# Schematic.net
KiCad netlist of a schematic drawn in EAGLE
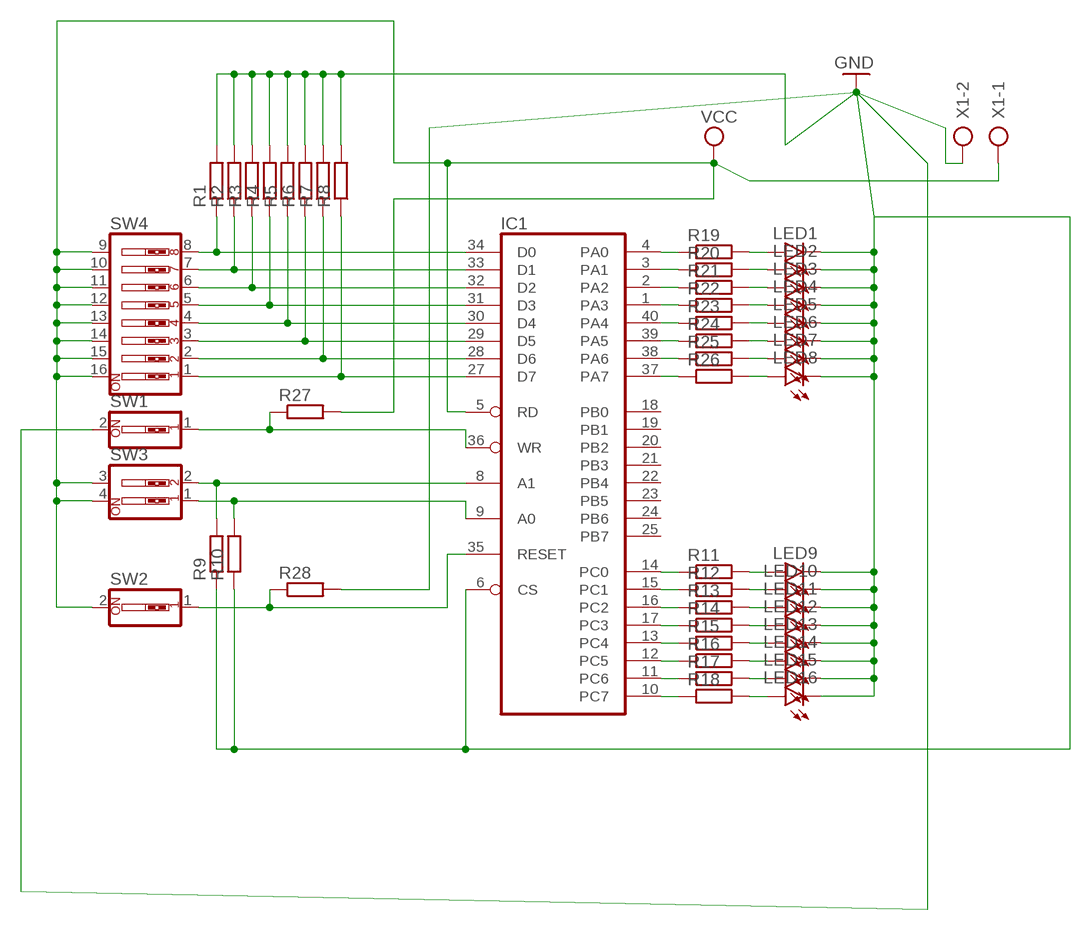
[diagram p0: schematic, sheet 1]

(export (version "E")
  (design (tool "Eeschema 10.0.6"))
  (components
    (comp (ref "IC1")
      (value "8255A")
      (footprint "eagle-import:DIL40")
      (libsource (lib "eagle-import") (part "8255A"))
    )
    (comp (ref "LED1")
      (value "LED5MM")
      (footprint "eagle-import:LED5MM")
      (libsource (lib "eagle-import") (part "LED5MM"))
    )
    (comp (ref "LED2")
      (value "LED5MM")
      (footprint "eagle-import:LED5MM")
      (libsource (lib "eagle-import") (part "LED5MM"))
    )
    (comp (ref "LED3")
      (value "LED5MM")
      (footprint "eagle-import:LED5MM")
      (libsource (lib "eagle-import") (part "LED5MM"))
    )
    (comp (ref "LED4")
      (value "LED5MM")
      (footprint "eagle-import:LED5MM")
      (libsource (lib "eagle-import") (part "LED5MM"))
    )
    (comp (ref "LED5")
      (value "LED5MM")
      (footprint "eagle-import:LED5MM")
      (libsource (lib "eagle-import") (part "LED5MM"))
    )
    (comp (ref "LED6")
      (value "LED5MM")
      (footprint "eagle-import:LED5MM")
      (libsource (lib "eagle-import") (part "LED5MM"))
    )
    (comp (ref "LED7")
      (value "LED5MM")
      (footprint "eagle-import:LED5MM")
      (libsource (lib "eagle-import") (part "LED5MM"))
    )
    (comp (ref "LED8")
      (value "LED5MM")
      (footprint "eagle-import:LED5MM")
      (libsource (lib "eagle-import") (part "LED5MM"))
    )
    (comp (ref "LED9")
      (value "LED5MM")
      (footprint "eagle-import:LED5MM")
      (libsource (lib "eagle-import") (part "LED5MM"))
    )
    (comp (ref "LED10")
      (value "LED5MM")
      (footprint "eagle-import:LED5MM")
      (libsource (lib "eagle-import") (part "LED5MM"))
    )
    (comp (ref "LED11")
      (value "LED5MM")
      (footprint "eagle-import:LED5MM")
      (libsource (lib "eagle-import") (part "LED5MM"))
    )
    (comp (ref "LED12")
      (value "LED5MM")
      (footprint "eagle-import:LED5MM")
      (libsource (lib "eagle-import") (part "LED5MM"))
    )
    (comp (ref "LED13")
      (value "LED5MM")
      (footprint "eagle-import:LED5MM")
      (libsource (lib "eagle-import") (part "LED5MM"))
    )
    (comp (ref "LED14")
      (value "LED5MM")
      (footprint "eagle-import:LED5MM")
      (libsource (lib "eagle-import") (part "LED5MM"))
    )
    (comp (ref "LED15")
      (value "LED5MM")
      (footprint "eagle-import:LED5MM")
      (libsource (lib "eagle-import") (part "LED5MM"))
    )
    (comp (ref "LED16")
      (value "LED5MM")
      (footprint "eagle-import:LED5MM")
      (libsource (lib "eagle-import") (part "LED5MM"))
    )
    (comp (ref "R1")
      (value "R-EU_0207/10")
      (footprint "eagle-import:0207_10")
      (libsource (lib "eagle-import") (part "R-EU_0207/10"))
    )
    (comp (ref "R2")
      (value "R-EU_0207/10")
      (footprint "eagle-import:0207_10")
      (libsource (lib "eagle-import") (part "R-EU_0207/10"))
    )
    (comp (ref "R3")
      (value "R-EU_0207/10")
      (footprint "eagle-import:0207_10")
      (libsource (lib "eagle-import") (part "R-EU_0207/10"))
    )
    (comp (ref "R4")
      (value "R-EU_0207/10")
      (footprint "eagle-import:0207_10")
      (libsource (lib "eagle-import") (part "R-EU_0207/10"))
    )
    (comp (ref "R5")
      (value "R-EU_0207/10")
      (footprint "eagle-import:0207_10")
      (libsource (lib "eagle-import") (part "R-EU_0207/10"))
    )
    (comp (ref "R6")
      (value "R-EU_0207/10")
      (footprint "eagle-import:0207_10")
      (libsource (lib "eagle-import") (part "R-EU_0207/10"))
    )
    (comp (ref "R7")
      (value "R-EU_0207/10")
      (footprint "eagle-import:0207_10")
      (libsource (lib "eagle-import") (part "R-EU_0207/10"))
    )
    (comp (ref "R8")
      (value "R-EU_0207/10")
      (footprint "eagle-import:0207_10")
      (libsource (lib "eagle-import") (part "R-EU_0207/10"))
    )
    (comp (ref "R9")
      (value "R-EU_0207/10")
      (footprint "eagle-import:0207_10")
      (libsource (lib "eagle-import") (part "R-EU_0207/10"))
    )
    (comp (ref "R10")
      (value "R-EU_0207/10")
      (footprint "eagle-import:0207_10")
      (libsource (lib "eagle-import") (part "R-EU_0207/10"))
    )
    (comp (ref "R11")
      (value "R-EU_0207/10")
      (footprint "eagle-import:0207_10")
      (libsource (lib "eagle-import") (part "R-EU_0207/10"))
    )
    (comp (ref "R12")
      (value "R-EU_0207/10")
      (footprint "eagle-import:0207_10")
      (libsource (lib "eagle-import") (part "R-EU_0207/10"))
    )
    (comp (ref "R13")
      (value "R-EU_0207/10")
      (footprint "eagle-import:0207_10")
      (libsource (lib "eagle-import") (part "R-EU_0207/10"))
    )
    (comp (ref "R14")
      (value "R-EU_0207/10")
      (footprint "eagle-import:0207_10")
      (libsource (lib "eagle-import") (part "R-EU_0207/10"))
    )
    (comp (ref "R15")
      (value "R-EU_0207/10")
      (footprint "eagle-import:0207_10")
      (libsource (lib "eagle-import") (part "R-EU_0207/10"))
    )
    (comp (ref "R16")
      (value "R-EU_0207/10")
      (footprint "eagle-import:0207_10")
      (libsource (lib "eagle-import") (part "R-EU_0207/10"))
    )
    (comp (ref "R17")
      (value "R-EU_0207/10")
      (footprint "eagle-import:0207_10")
      (libsource (lib "eagle-import") (part "R-EU_0207/10"))
    )
    (comp (ref "R18")
      (value "R-EU_0207/10")
      (footprint "eagle-import:0207_10")
      (libsource (lib "eagle-import") (part "R-EU_0207/10"))
    )
    (comp (ref "R19")
      (value "R-EU_0207/10")
      (footprint "eagle-import:0207_10")
      (libsource (lib "eagle-import") (part "R-EU_0207/10"))
    )
    (comp (ref "R20")
      (value "R-EU_0207/10")
      (footprint "eagle-import:0207_10")
      (libsource (lib "eagle-import") (part "R-EU_0207/10"))
    )
    (comp (ref "R21")
      (value "R-EU_0207/10")
      (footprint "eagle-import:0207_10")
      (libsource (lib "eagle-import") (part "R-EU_0207/10"))
    )
    (comp (ref "R22")
      (value "R-EU_0207/10")
      (footprint "eagle-import:0207_10")
      (libsource (lib "eagle-import") (part "R-EU_0207/10"))
    )
    (comp (ref "R23")
      (value "R-EU_0207/10")
      (footprint "eagle-import:0207_10")
      (libsource (lib "eagle-import") (part "R-EU_0207/10"))
    )
    (comp (ref "R24")
      (value "R-EU_0207/10")
      (footprint "eagle-import:0207_10")
      (libsource (lib "eagle-import") (part "R-EU_0207/10"))
    )
    (comp (ref "R25")
      (value "R-EU_0207/10")
      (footprint "eagle-import:0207_10")
      (libsource (lib "eagle-import") (part "R-EU_0207/10"))
    )
    (comp (ref "R26")
      (value "R-EU_0207/10")
      (footprint "eagle-import:0207_10")
      (libsource (lib "eagle-import") (part "R-EU_0207/10"))
    )
    (comp (ref "R27")
      (value "R-EU_0207/10")
      (footprint "eagle-import:0207_10")
      (libsource (lib "eagle-import") (part "R-EU_0207/10"))
    )
    (comp (ref "R28")
      (value "R-EU_0207/10")
      (footprint "eagle-import:0207_10")
      (libsource (lib "eagle-import") (part "R-EU_0207/10"))
    )
    (comp (ref "SW1")
      (value "SW_DIP-1")
      (footprint "eagle-import:EDG-01")
      (libsource (lib "eagle-import") (part "SW_DIP-1"))
    )
    (comp (ref "SW2")
      (value "SW_DIP-1")
      (footprint "eagle-import:EDG-01")
      (libsource (lib "eagle-import") (part "SW_DIP-1"))
    )
    (comp (ref "SW3")
      (value "SW_DIP-2")
      (footprint "eagle-import:EDG-02")
      (libsource (lib "eagle-import") (part "SW_DIP-2"))
    )
    (comp (ref "SW4")
      (value "SW_DIP-8")
      (footprint "eagle-import:EDG-08")
      (libsource (lib "eagle-import") (part "SW_DIP-8"))
    )
    (comp (ref "X1")
      (value "AK500/2")
      (footprint "eagle-import:AK500_2")
      (libsource (lib "eagle-import") (part "AK500/2"))
    )
  )
  (nets
    (net (code "1") (name "GND") (class "Default")
      (node (ref "IC1") (pin "6") (pinfunction "CS_6") (pintype "input"))
      (node (ref "LED1") (pin "K") (pinfunction "C_K") (pintype "passive"))
      (node (ref "LED10") (pin "K") (pinfunction "C_K") (pintype "passive"))
      (node (ref "LED11") (pin "K") (pinfunction "C_K") (pintype "passive"))
      (node (ref "LED12") (pin "K") (pinfunction "C_K") (pintype "passive"))
      (node (ref "LED13") (pin "K") (pinfunction "C_K") (pintype "passive"))
      (node (ref "LED14") (pin "K") (pinfunction "C_K") (pintype "passive"))
      (node (ref "LED15") (pin "K") (pinfunction "C_K") (pintype "passive"))
      (node (ref "LED16") (pin "K") (pinfunction "C_K") (pintype "passive"))
      (node (ref "LED2") (pin "K") (pinfunction "C_K") (pintype "passive"))
      (node (ref "LED3") (pin "K") (pinfunction "C_K") (pintype "passive"))
      (node (ref "LED4") (pin "K") (pinfunction "C_K") (pintype "passive"))
      (node (ref "LED5") (pin "K") (pinfunction "C_K") (pintype "passive"))
      (node (ref "LED6") (pin "K") (pinfunction "C_K") (pintype "passive"))
      (node (ref "LED7") (pin "K") (pinfunction "C_K") (pintype "passive"))
      (node (ref "LED8") (pin "K") (pinfunction "C_K") (pintype "passive"))
      (node (ref "LED9") (pin "K") (pinfunction "C_K") (pintype "passive"))
      (node (ref "R1") (pin "2") (pinfunction "2_2") (pintype "passive"))
      (node (ref "R10") (pin "1") (pinfunction "1_1") (pintype "passive"))
      (node (ref "R2") (pin "2") (pinfunction "2_2") (pintype "passive"))
      (node (ref "R28") (pin "2") (pinfunction "2_2") (pintype "passive"))
      (node (ref "R3") (pin "2") (pinfunction "2_2") (pintype "passive"))
      (node (ref "R4") (pin "2") (pinfunction "2_2") (pintype "passive"))
      (node (ref "R5") (pin "2") (pinfunction "2_2") (pintype "passive"))
      (node (ref "R6") (pin "2") (pinfunction "2_2") (pintype "passive"))
      (node (ref "R7") (pin "2") (pinfunction "2_2") (pintype "passive"))
      (node (ref "R8") (pin "2") (pinfunction "2_2") (pintype "passive"))
      (node (ref "R9") (pin "1") (pinfunction "1_1") (pintype "passive"))
      (node (ref "SW1") (pin "2") (pinfunction "2_2") (pintype "passive"))
      (node (ref "X1") (pin "2") (pinfunction "KL_2") (pintype "passive"))
    )
    (net (code "2") (name "Net-(IC1A-A0)") (class "Default")
      (node (ref "IC1") (pin "9") (pinfunction "A0_9") (pintype "input"))
      (node (ref "R10") (pin "2") (pinfunction "2_2") (pintype "passive"))
      (node (ref "SW3") (pin "1") (pinfunction "1_1") (pintype "passive"))
    )
    (net (code "3") (name "Net-(IC1A-A1)") (class "Default")
      (node (ref "IC1") (pin "8") (pinfunction "A1_8") (pintype "input"))
      (node (ref "R9") (pin "2") (pinfunction "2_2") (pintype "passive"))
      (node (ref "SW3") (pin "2") (pinfunction "2_2") (pintype "passive"))
    )
    (net (code "4") (name "Net-(IC1A-D0)") (class "Default")
      (node (ref "IC1") (pin "34") (pinfunction "D0_34") (pintype "bidirectional"))
      (node (ref "R1") (pin "1") (pinfunction "1_1") (pintype "passive"))
      (node (ref "SW4") (pin "8") (pinfunction "8_8") (pintype "passive"))
    )
    (net (code "5") (name "Net-(IC1A-D1)") (class "Default")
      (node (ref "IC1") (pin "33") (pinfunction "D1_33") (pintype "bidirectional"))
      (node (ref "R2") (pin "1") (pinfunction "1_1") (pintype "passive"))
      (node (ref "SW4") (pin "7") (pinfunction "7_7") (pintype "passive"))
    )
    (net (code "6") (name "Net-(IC1A-D2)") (class "Default")
      (node (ref "IC1") (pin "32") (pinfunction "D2_32") (pintype "bidirectional"))
      (node (ref "R3") (pin "1") (pinfunction "1_1") (pintype "passive"))
      (node (ref "SW4") (pin "6") (pinfunction "6_6") (pintype "passive"))
    )
    (net (code "7") (name "Net-(IC1A-D3)") (class "Default")
      (node (ref "IC1") (pin "31") (pinfunction "D3_31") (pintype "bidirectional"))
      (node (ref "R4") (pin "1") (pinfunction "1_1") (pintype "passive"))
      (node (ref "SW4") (pin "5") (pinfunction "5_5") (pintype "passive"))
    )
    (net (code "8") (name "Net-(IC1A-D4)") (class "Default")
      (node (ref "IC1") (pin "30") (pinfunction "D4_30") (pintype "bidirectional"))
      (node (ref "R5") (pin "1") (pinfunction "1_1") (pintype "passive"))
      (node (ref "SW4") (pin "4") (pinfunction "4_4") (pintype "passive"))
    )
    (net (code "9") (name "Net-(IC1A-D5)") (class "Default")
      (node (ref "IC1") (pin "29") (pinfunction "D5_29") (pintype "bidirectional"))
      (node (ref "R6") (pin "1") (pinfunction "1_1") (pintype "passive"))
      (node (ref "SW4") (pin "3") (pinfunction "3_3") (pintype "passive"))
    )
    (net (code "10") (name "Net-(IC1A-D6)") (class "Default")
      (node (ref "IC1") (pin "28") (pinfunction "D6_28") (pintype "bidirectional"))
      (node (ref "R7") (pin "1") (pinfunction "1_1") (pintype "passive"))
      (node (ref "SW4") (pin "2") (pinfunction "2_2") (pintype "passive"))
    )
    (net (code "11") (name "Net-(IC1A-D7)") (class "Default")
      (node (ref "IC1") (pin "27") (pinfunction "D7_27") (pintype "bidirectional"))
      (node (ref "R8") (pin "1") (pinfunction "1_1") (pintype "passive"))
      (node (ref "SW4") (pin "1") (pinfunction "1_1") (pintype "passive"))
    )
    (net (code "12") (name "Net-(IC1A-PA0)") (class "Default")
      (node (ref "IC1") (pin "4") (pinfunction "PA0_4") (pintype "bidirectional"))
      (node (ref "R19") (pin "1") (pinfunction "1_1") (pintype "passive"))
    )
    (net (code "13") (name "Net-(IC1A-PA1)") (class "Default")
      (node (ref "IC1") (pin "3") (pinfunction "PA1_3") (pintype "bidirectional"))
      (node (ref "R20") (pin "1") (pinfunction "1_1") (pintype "passive"))
    )
    (net (code "14") (name "Net-(IC1A-PA2)") (class "Default")
      (node (ref "IC1") (pin "2") (pinfunction "PA2_2") (pintype "bidirectional"))
      (node (ref "R21") (pin "1") (pinfunction "1_1") (pintype "passive"))
    )
    (net (code "15") (name "Net-(IC1A-PA3)") (class "Default")
      (node (ref "IC1") (pin "1") (pinfunction "PA3_1") (pintype "bidirectional"))
      (node (ref "R22") (pin "1") (pinfunction "1_1") (pintype "passive"))
    )
    (net (code "16") (name "Net-(IC1A-PA4)") (class "Default")
      (node (ref "IC1") (pin "40") (pinfunction "PA4_40") (pintype "bidirectional"))
      (node (ref "R23") (pin "1") (pinfunction "1_1") (pintype "passive"))
    )
    (net (code "17") (name "Net-(IC1A-PA5)") (class "Default")
      (node (ref "IC1") (pin "39") (pinfunction "PA5_39") (pintype "bidirectional"))
      (node (ref "R24") (pin "1") (pinfunction "1_1") (pintype "passive"))
    )
    (net (code "18") (name "Net-(IC1A-PA6)") (class "Default")
      (node (ref "IC1") (pin "38") (pinfunction "PA6_38") (pintype "bidirectional"))
      (node (ref "R25") (pin "1") (pinfunction "1_1") (pintype "passive"))
    )
    (net (code "19") (name "Net-(IC1A-PA7)") (class "Default")
      (node (ref "IC1") (pin "37") (pinfunction "PA7_37") (pintype "bidirectional"))
      (node (ref "R26") (pin "1") (pinfunction "1_1") (pintype "passive"))
    )
    (net (code "20") (name "Net-(IC1A-PC0)") (class "Default")
      (node (ref "IC1") (pin "14") (pinfunction "PC0_14") (pintype "bidirectional"))
      (node (ref "R11") (pin "1") (pinfunction "1_1") (pintype "passive"))
    )
    (net (code "21") (name "Net-(IC1A-PC1)") (class "Default")
      (node (ref "IC1") (pin "15") (pinfunction "PC1_15") (pintype "bidirectional"))
      (node (ref "R12") (pin "1") (pinfunction "1_1") (pintype "passive"))
    )
    (net (code "22") (name "Net-(IC1A-PC2)") (class "Default")
      (node (ref "IC1") (pin "16") (pinfunction "PC2_16") (pintype "bidirectional"))
      (node (ref "R13") (pin "1") (pinfunction "1_1") (pintype "passive"))
    )
    (net (code "23") (name "Net-(IC1A-PC3)") (class "Default")
      (node (ref "IC1") (pin "17") (pinfunction "PC3_17") (pintype "bidirectional"))
      (node (ref "R14") (pin "1") (pinfunction "1_1") (pintype "passive"))
    )
    (net (code "24") (name "Net-(IC1A-PC4)") (class "Default")
      (node (ref "IC1") (pin "13") (pinfunction "PC4_13") (pintype "bidirectional"))
      (node (ref "R15") (pin "1") (pinfunction "1_1") (pintype "passive"))
    )
    (net (code "25") (name "Net-(IC1A-PC5)") (class "Default")
      (node (ref "IC1") (pin "12") (pinfunction "PC5_12") (pintype "bidirectional"))
      (node (ref "R16") (pin "1") (pinfunction "1_1") (pintype "passive"))
    )
    (net (code "26") (name "Net-(IC1A-PC6)") (class "Default")
      (node (ref "IC1") (pin "11") (pinfunction "PC6_11") (pintype "bidirectional"))
      (node (ref "R17") (pin "1") (pinfunction "1_1") (pintype "passive"))
    )
    (net (code "27") (name "Net-(IC1A-PC7)") (class "Default")
      (node (ref "IC1") (pin "10") (pinfunction "PC7_10") (pintype "bidirectional"))
      (node (ref "R18") (pin "1") (pinfunction "1_1") (pintype "passive"))
    )
    (net (code "28") (name "Net-(IC1A-RESET)") (class "Default")
      (node (ref "IC1") (pin "35") (pinfunction "RESET_35") (pintype "input"))
      (node (ref "R28") (pin "1") (pinfunction "1_1") (pintype "passive"))
      (node (ref "SW2") (pin "1") (pinfunction "1_1") (pintype "passive"))
    )
    (net (code "29") (name "Net-(IC1A-WR)") (class "Default")
      (node (ref "IC1") (pin "36") (pinfunction "WR_36") (pintype "input"))
      (node (ref "R27") (pin "1") (pinfunction "1_1") (pintype "passive"))
      (node (ref "SW1") (pin "1") (pinfunction "1_1") (pintype "passive"))
    )
    (net (code "30") (name "Net-(LED1-PadA)") (class "Default")
      (node (ref "LED1") (pin "A") (pinfunction "A_A") (pintype "passive"))
      (node (ref "R19") (pin "2") (pinfunction "2_2") (pintype "passive"))
    )
    (net (code "31") (name "Net-(LED2-PadA)") (class "Default")
      (node (ref "LED2") (pin "A") (pinfunction "A_A") (pintype "passive"))
      (node (ref "R20") (pin "2") (pinfunction "2_2") (pintype "passive"))
    )
    (net (code "32") (name "Net-(LED3-PadA)") (class "Default")
      (node (ref "LED3") (pin "A") (pinfunction "A_A") (pintype "passive"))
      (node (ref "R21") (pin "2") (pinfunction "2_2") (pintype "passive"))
    )
    (net (code "33") (name "Net-(LED4-PadA)") (class "Default")
      (node (ref "LED4") (pin "A") (pinfunction "A_A") (pintype "passive"))
      (node (ref "R22") (pin "2") (pinfunction "2_2") (pintype "passive"))
    )
    (net (code "34") (name "Net-(LED5-PadA)") (class "Default")
      (node (ref "LED5") (pin "A") (pinfunction "A_A") (pintype "passive"))
      (node (ref "R23") (pin "2") (pinfunction "2_2") (pintype "passive"))
    )
    (net (code "35") (name "Net-(LED6-PadA)") (class "Default")
      (node (ref "LED6") (pin "A") (pinfunction "A_A") (pintype "passive"))
      (node (ref "R24") (pin "2") (pinfunction "2_2") (pintype "passive"))
    )
    (net (code "36") (name "Net-(LED7-PadA)") (class "Default")
      (node (ref "LED7") (pin "A") (pinfunction "A_A") (pintype "passive"))
      (node (ref "R25") (pin "2") (pinfunction "2_2") (pintype "passive"))
    )
    (net (code "37") (name "Net-(LED8-PadA)") (class "Default")
      (node (ref "LED8") (pin "A") (pinfunction "A_A") (pintype "passive"))
      (node (ref "R26") (pin "2") (pinfunction "2_2") (pintype "passive"))
    )
    (net (code "38") (name "Net-(LED9-PadA)") (class "Default")
      (node (ref "LED9") (pin "A") (pinfunction "A_A") (pintype "passive"))
      (node (ref "R11") (pin "2") (pinfunction "2_2") (pintype "passive"))
    )
    (net (code "39") (name "Net-(LED10-PadA)") (class "Default")
      (node (ref "LED10") (pin "A") (pinfunction "A_A") (pintype "passive"))
      (node (ref "R12") (pin "2") (pinfunction "2_2") (pintype "passive"))
    )
    (net (code "40") (name "Net-(LED11-PadA)") (class "Default")
      (node (ref "LED11") (pin "A") (pinfunction "A_A") (pintype "passive"))
      (node (ref "R13") (pin "2") (pinfunction "2_2") (pintype "passive"))
    )
    (net (code "41") (name "Net-(LED12-PadA)") (class "Default")
      (node (ref "LED12") (pin "A") (pinfunction "A_A") (pintype "passive"))
      (node (ref "R14") (pin "2") (pinfunction "2_2") (pintype "passive"))
    )
    (net (code "42") (name "Net-(LED13-PadA)") (class "Default")
      (node (ref "LED13") (pin "A") (pinfunction "A_A") (pintype "passive"))
      (node (ref "R15") (pin "2") (pinfunction "2_2") (pintype "passive"))
    )
    (net (code "43") (name "Net-(LED14-PadA)") (class "Default")
      (node (ref "LED14") (pin "A") (pinfunction "A_A") (pintype "passive"))
      (node (ref "R16") (pin "2") (pinfunction "2_2") (pintype "passive"))
    )
    (net (code "44") (name "Net-(LED15-PadA)") (class "Default")
      (node (ref "LED15") (pin "A") (pinfunction "A_A") (pintype "passive"))
      (node (ref "R17") (pin "2") (pinfunction "2_2") (pintype "passive"))
    )
    (net (code "45") (name "Net-(LED16-PadA)") (class "Default")
      (node (ref "LED16") (pin "A") (pinfunction "A_A") (pintype "passive"))
      (node (ref "R18") (pin "2") (pinfunction "2_2") (pintype "passive"))
    )
    (net (code "46") (name "VCC") (class "Default")
      (node (ref "IC1") (pin "5") (pinfunction "RD_5") (pintype "input"))
      (node (ref "R27") (pin "2") (pinfunction "2_2") (pintype "passive"))
      (node (ref "SW2") (pin "2") (pinfunction "2_2") (pintype "passive"))
      (node (ref "SW3") (pin "3") (pinfunction "3_3") (pintype "passive"))
      (node (ref "SW3") (pin "4") (pinfunction "4_4") (pintype "passive"))
      (node (ref "SW4") (pin "10") (pinfunction "10_10") (pintype "passive"))
      (node (ref "SW4") (pin "11") (pinfunction "11_11") (pintype "passive"))
      (node (ref "SW4") (pin "12") (pinfunction "12_12") (pintype "passive"))
      (node (ref "SW4") (pin "13") (pinfunction "13_13") (pintype "passive"))
      (node (ref "SW4") (pin "14") (pinfunction "14_14") (pintype "passive"))
      (node (ref "SW4") (pin "15") (pinfunction "15_15") (pintype "passive"))
      (node (ref "SW4") (pin "16") (pinfunction "16_16") (pintype "passive"))
      (node (ref "SW4") (pin "9") (pinfunction "9_9") (pintype "passive"))
      (node (ref "X1") (pin "1") (pinfunction "KL_1") (pintype "passive"))
    )
    (net (code "47") (name "unconnected-(IC1A-PB0-Pad18)") (class "Default")
      (node (ref "IC1") (pin "18") (pinfunction "PB0_18") (pintype "bidirectional"))
    )
    (net (code "48") (name "unconnected-(IC1A-PB1-Pad19)") (class "Default")
      (node (ref "IC1") (pin "19") (pinfunction "PB1_19") (pintype "bidirectional"))
    )
    (net (code "49") (name "unconnected-(IC1A-PB2-Pad20)") (class "Default")
      (node (ref "IC1") (pin "20") (pinfunction "PB2_20") (pintype "bidirectional"))
    )
    (net (code "50") (name "unconnected-(IC1A-PB3-Pad21)") (class "Default")
      (node (ref "IC1") (pin "21") (pinfunction "PB3_21") (pintype "bidirectional"))
    )
    (net (code "51") (name "unconnected-(IC1A-PB4-Pad22)") (class "Default")
      (node (ref "IC1") (pin "22") (pinfunction "PB4_22") (pintype "bidirectional"))
    )
    (net (code "52") (name "unconnected-(IC1A-PB5-Pad23)") (class "Default")
      (node (ref "IC1") (pin "23") (pinfunction "PB5_23") (pintype "bidirectional"))
    )
    (net (code "53") (name "unconnected-(IC1A-PB6-Pad24)") (class "Default")
      (node (ref "IC1") (pin "24") (pinfunction "PB6_24") (pintype "bidirectional"))
    )
    (net (code "54") (name "unconnected-(IC1A-PB7-Pad25)") (class "Default")
      (node (ref "IC1") (pin "25") (pinfunction "PB7_25") (pintype "bidirectional"))
    )
  )
)
